# DDR4.net
KiCad netlist of a schematic drawn in Altium Designer
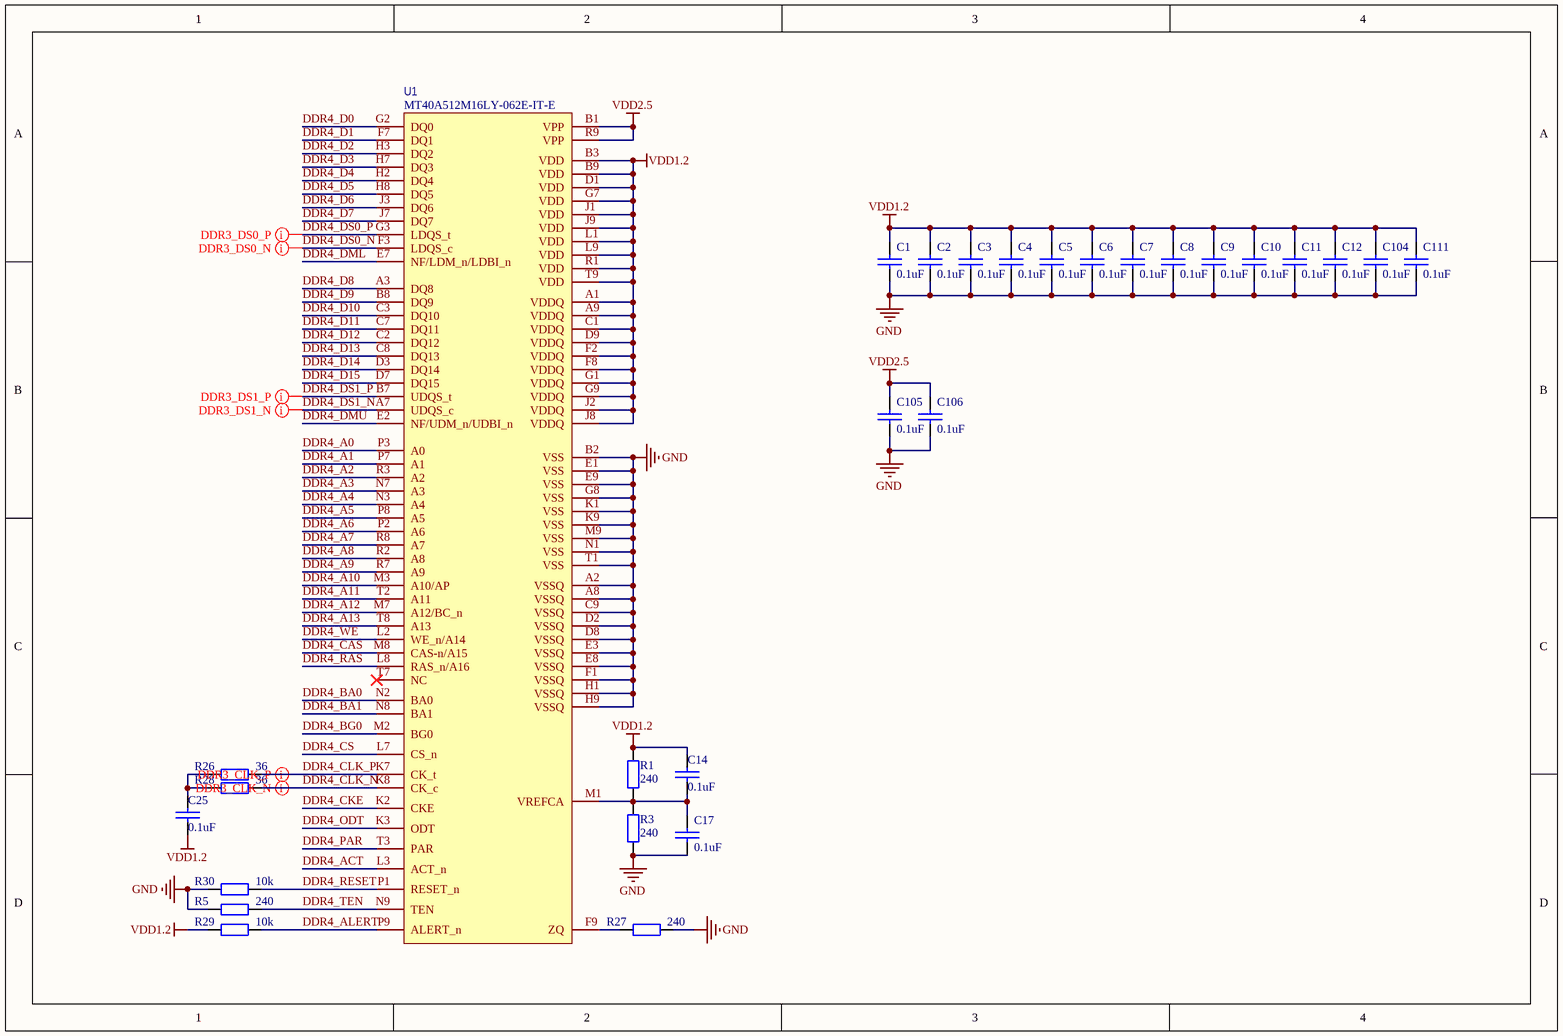
[diagram p0: DDR4.SchDoc]

(export (version "E")
  (design (tool "Eeschema 10.0.6"))
  (components
    (comp (ref "C1") (value "0.1uF") (footprint "0402_c_m") (libsource (lib "My library") (part "CAP")))
    (comp (ref "C2") (value "0.1uF") (footprint "0402_c_m") (libsource (lib "My library") (part "CAP")))
    (comp (ref "C3") (value "0.1uF") (footprint "0402_c_m") (libsource (lib "My library") (part "CAP")))
    (comp (ref "C4") (value "0.1uF") (footprint "0402_c_m") (libsource (lib "My library") (part "CAP")))
    (comp (ref "C5") (value "0.1uF") (footprint "0402_c_m") (libsource (lib "My library") (part "CAP")))
    (comp (ref "C6") (value "0.1uF") (footprint "0402_c_m") (libsource (lib "My library") (part "CAP")))
    (comp (ref "C7") (value "0.1uF") (footprint "0402_c_m") (libsource (lib "My library") (part "CAP")))
    (comp (ref "C8") (value "0.1uF") (footprint "0402_c_m") (libsource (lib "My library") (part "CAP")))
    (comp (ref "C9") (value "0.1uF") (footprint "0402_c_m") (libsource (lib "My library") (part "CAP")))
    (comp (ref "C10") (value "0.1uF") (footprint "0402_c_m") (libsource (lib "My library") (part "CAP")))
    (comp (ref "C11") (value "0.1uF") (footprint "0402_c_m") (libsource (lib "My library") (part "CAP")))
    (comp (ref "C12") (value "0.1uF") (footprint "0402_c_m") (libsource (lib "My library") (part "CAP")))
    (comp (ref "C14") (value "0.1uF") (footprint "0402_c_m") (libsource (lib "My library") (part "CAP")))
    (comp (ref "C17") (value "0.1uF") (footprint "0402_c_m") (libsource (lib "My library") (part "CAP")))
    (comp (ref "C25") (value "0.1uF") (footprint "0402_c_m") (libsource (lib "My library") (part "CAP")))
    (comp (ref "C104") (value "0.1uF") (footprint "0402_c_m") (libsource (lib "My library") (part "CAP")))
    (comp (ref "C105") (value "0.1uF") (footprint "0402_c_m") (libsource (lib "My library") (part "CAP")))
    (comp (ref "C106") (value "0.1uF") (footprint "0402_c_m") (libsource (lib "My library") (part "CAP")))
    (comp (ref "C111") (value "0.1uF") (footprint "0402_c_m") (libsource (lib "My library") (part "CAP")))
    (comp (ref "R1") (value "240") (footprint "0402_r_m") (libsource (lib "My Library") (part "RES2")))
    (comp (ref "R3") (value "240") (footprint "0402_r_m") (libsource (lib "My Library") (part "RES2")))
    (comp (ref "R5") (value "240") (footprint "0402_R_M") (libsource (lib "Common") (part "RES2")))
    (comp (ref "R26") (value "36") (footprint "0402_r_m") (libsource (lib "My Library") (part "RES2")))
    (comp (ref "R27") (value "240") (footprint "0402_R_M") (libsource (lib "Common") (part "RES2")))
    (comp (ref "R28") (value "36") (footprint "0402_r_m") (libsource (lib "My Library") (part "RES2")))
    (comp (ref "R29") (value "10k") (footprint "0402_r_m") (libsource (lib "My Library") (part "RES2")))
    (comp (ref "R30") (value "10k") (footprint "0402_r_m") (libsource (lib "My Library") (part "RES2")))
    (comp (ref "U1")
      (value "MT40A512M16LY-062E-IT-E")
      (footprint "MT40A512M16LY-062E-IT-E")
      (libsource (lib "MT40A512M16LY-062E-IT-E") (part "MT40A512M16LY-062E IT{colon}E"))
    )
  )
  (nets
    (net (code "1") (name "/DDR4_A0") (class "Default")
      (node (ref "U1") (pin "P3") (pinfunction "A0_P3") (pintype "passive"))
    )
    (net (code "2") (name "/DDR4_A1") (class "Default")
      (node (ref "U1") (pin "P7") (pinfunction "A1_P7") (pintype "passive"))
    )
    (net (code "3") (name "/DDR4_A2") (class "Default")
      (node (ref "U1") (pin "R3") (pinfunction "A2_R3") (pintype "passive"))
    )
    (net (code "4") (name "/DDR4_A3") (class "Default")
      (node (ref "U1") (pin "N7") (pinfunction "A3_N7") (pintype "passive"))
    )
    (net (code "5") (name "/DDR4_A4") (class "Default")
      (node (ref "U1") (pin "N3") (pinfunction "A4_N3") (pintype "passive"))
    )
    (net (code "6") (name "/DDR4_A5") (class "Default")
      (node (ref "U1") (pin "P8") (pinfunction "A5_P8") (pintype "passive"))
    )
    (net (code "7") (name "/DDR4_A6") (class "Default")
      (node (ref "U1") (pin "P2") (pinfunction "A6_P2") (pintype "passive"))
    )
    (net (code "8") (name "/DDR4_A7") (class "Default")
      (node (ref "U1") (pin "R8") (pinfunction "A7_R8") (pintype "passive"))
    )
    (net (code "9") (name "/DDR4_A8") (class "Default")
      (node (ref "U1") (pin "R2") (pinfunction "A8_R2") (pintype "passive"))
    )
    (net (code "10") (name "/DDR4_A9") (class "Default")
      (node (ref "U1") (pin "R7") (pinfunction "A9_R7") (pintype "passive"))
    )
    (net (code "11") (name "/DDR4_A10") (class "Default")
      (node (ref "U1") (pin "M3") (pinfunction "A10/AP_M3") (pintype "passive"))
    )
    (net (code "12") (name "/DDR4_A11") (class "Default")
      (node (ref "U1") (pin "T2") (pinfunction "A11_T2") (pintype "passive"))
    )
    (net (code "13") (name "/DDR4_A12") (class "Default")
      (node (ref "U1") (pin "M7") (pinfunction "A12/BC_n_M7") (pintype "passive"))
    )
    (net (code "14") (name "/DDR4_A13") (class "Default")
      (node (ref "U1") (pin "T8") (pinfunction "A13_T8") (pintype "passive"))
    )
    (net (code "15") (name "/DDR4_ACT") (class "Default")
      (node (ref "U1") (pin "L3") (pinfunction "ACT_n_L3") (pintype "passive"))
    )
    (net (code "16") (name "/DDR4_ALERT") (class "Default")
      (node (ref "R29") (pin "1") (pintype "passive"))
      (node (ref "U1") (pin "P9") (pinfunction "ALERT_n_P9") (pintype "passive"))
    )
    (net (code "17") (name "/DDR4_BA0") (class "Default")
      (node (ref "U1") (pin "N2") (pinfunction "BA0_N2") (pintype "passive"))
    )
    (net (code "18") (name "/DDR4_BA1") (class "Default")
      (node (ref "U1") (pin "N8") (pinfunction "BA1_N8") (pintype "passive"))
    )
    (net (code "19") (name "/DDR4_BG0") (class "Default")
      (node (ref "U1") (pin "M2") (pinfunction "BG0_M2") (pintype "passive"))
    )
    (net (code "20") (name "/DDR4_CAS") (class "Default")
      (node (ref "U1") (pin "M8") (pinfunction "CAS-n/A15_M8") (pintype "passive"))
    )
    (net (code "21") (name "/DDR4_CKE") (class "Default")
      (node (ref "U1") (pin "K2") (pinfunction "CKE_K2") (pintype "passive"))
    )
    (net (code "22") (name "/DDR4_CLK_N") (class "Default")
      (node (ref "R28") (pin "2") (pintype "passive"))
      (node (ref "U1") (pin "K8") (pinfunction "CK_c_K8") (pintype "passive"))
    )
    (net (code "23") (name "/DDR4_CLK_P") (class "Default")
      (node (ref "R26") (pin "2") (pintype "passive"))
      (node (ref "U1") (pin "K7") (pinfunction "CK_t_K7") (pintype "passive"))
    )
    (net (code "24") (name "/DDR4_CS") (class "Default")
      (node (ref "U1") (pin "L7") (pinfunction "CS_n_L7") (pintype "passive"))
    )
    (net (code "25") (name "/DDR4_D0") (class "Default")
      (node (ref "U1") (pin "G2") (pinfunction "DQ0_G2") (pintype "passive"))
    )
    (net (code "26") (name "/DDR4_D1") (class "Default")
      (node (ref "U1") (pin "F7") (pinfunction "DQ1_F7") (pintype "passive"))
    )
    (net (code "27") (name "/DDR4_D2") (class "Default")
      (node (ref "U1") (pin "H3") (pinfunction "DQ2_H3") (pintype "passive"))
    )
    (net (code "28") (name "/DDR4_D3") (class "Default")
      (node (ref "U1") (pin "H7") (pinfunction "DQ3_H7") (pintype "passive"))
    )
    (net (code "29") (name "/DDR4_D4") (class "Default")
      (node (ref "U1") (pin "H2") (pinfunction "DQ4_H2") (pintype "passive"))
    )
    (net (code "30") (name "/DDR4_D5") (class "Default")
      (node (ref "U1") (pin "H8") (pinfunction "DQ5_H8") (pintype "passive"))
    )
    (net (code "31") (name "/DDR4_D6") (class "Default")
      (node (ref "U1") (pin "J3") (pinfunction "DQ6_J3") (pintype "passive"))
    )
    (net (code "32") (name "/DDR4_D7") (class "Default")
      (node (ref "U1") (pin "J7") (pinfunction "DQ7_J7") (pintype "passive"))
    )
    (net (code "33") (name "/DDR4_D8") (class "Default")
      (node (ref "U1") (pin "A3") (pinfunction "DQ8_A3") (pintype "passive"))
    )
    (net (code "34") (name "/DDR4_D9") (class "Default")
      (node (ref "U1") (pin "B8") (pinfunction "DQ9_B8") (pintype "passive"))
    )
    (net (code "35") (name "/DDR4_D10") (class "Default")
      (node (ref "U1") (pin "C3") (pinfunction "DQ10_C3") (pintype "passive"))
    )
    (net (code "36") (name "/DDR4_D11") (class "Default")
      (node (ref "U1") (pin "C7") (pinfunction "DQ11_C7") (pintype "passive"))
    )
    (net (code "37") (name "/DDR4_D12") (class "Default")
      (node (ref "U1") (pin "C2") (pinfunction "DQ12_C2") (pintype "passive"))
    )
    (net (code "38") (name "/DDR4_D13") (class "Default")
      (node (ref "U1") (pin "C8") (pinfunction "DQ13_C8") (pintype "passive"))
    )
    (net (code "39") (name "/DDR4_D14") (class "Default")
      (node (ref "U1") (pin "D3") (pinfunction "DQ14_D3") (pintype "passive"))
    )
    (net (code "40") (name "/DDR4_D15") (class "Default")
      (node (ref "U1") (pin "D7") (pinfunction "DQ15_D7") (pintype "passive"))
    )
    (net (code "41") (name "/DDR4_DML") (class "Default")
      (node (ref "U1") (pin "E7") (pinfunction "NF/LDM_n/LDBI_n_E7") (pintype "passive"))
    )
    (net (code "42") (name "/DDR4_DMU") (class "Default")
      (node (ref "U1") (pin "E2") (pinfunction "NF/UDM_n/UDBI_n_E2") (pintype "passive"))
    )
    (net (code "43") (name "/DDR4_DS0_N") (class "Default")
      (node (ref "U1") (pin "F3") (pinfunction "LDQS_c_F3") (pintype "passive"))
    )
    (net (code "44") (name "/DDR4_DS0_P") (class "Default")
      (node (ref "U1") (pin "G3") (pinfunction "LDQS_t_G3") (pintype "passive"))
    )
    (net (code "45") (name "/DDR4_DS1_N") (class "Default")
      (node (ref "U1") (pin "A7") (pinfunction "UDQS_c_A7") (pintype "passive"))
    )
    (net (code "46") (name "/DDR4_DS1_P") (class "Default")
      (node (ref "U1") (pin "B7") (pinfunction "UDQS_t_B7") (pintype "passive"))
    )
    (net (code "47") (name "/DDR4_ODT") (class "Default")
      (node (ref "U1") (pin "K3") (pinfunction "ODT_K3") (pintype "passive"))
    )
    (net (code "48") (name "/DDR4_PAR") (class "Default")
      (node (ref "U1") (pin "T3") (pinfunction "PAR_T3") (pintype "passive"))
    )
    (net (code "49") (name "/DDR4_RAS") (class "Default")
      (node (ref "U1") (pin "L8") (pinfunction "RAS_n/A16_L8") (pintype "passive"))
    )
    (net (code "50") (name "/DDR4_RESET") (class "Default")
      (node (ref "R30") (pin "1") (pintype "passive"))
      (node (ref "U1") (pin "P1") (pinfunction "RESET_n_P1") (pintype "passive"))
    )
    (net (code "51") (name "/DDR4_TEN") (class "Default")
      (node (ref "R5") (pin "1") (pintype "passive"))
      (node (ref "U1") (pin "N9") (pinfunction "TEN_N9") (pintype "passive"))
    )
    (net (code "52") (name "/DDR4_WE") (class "Default")
      (node (ref "U1") (pin "L2") (pinfunction "WE_n/A14_L2") (pintype "passive"))
    )
    (net (code "53") (name "GND") (class "Default")
      (node (ref "C1") (pin "2") (pinfunction "2_2") (pintype "passive"))
      (node (ref "C10") (pin "2") (pinfunction "2_2") (pintype "passive"))
      (node (ref "C104") (pin "2") (pinfunction "2_2") (pintype "passive"))
      (node (ref "C105") (pin "2") (pinfunction "2_2") (pintype "passive"))
      (node (ref "C106") (pin "2") (pinfunction "2_2") (pintype "passive"))
      (node (ref "C11") (pin "2") (pinfunction "2_2") (pintype "passive"))
      (node (ref "C111") (pin "2") (pinfunction "2_2") (pintype "passive"))
      (node (ref "C12") (pin "2") (pinfunction "2_2") (pintype "passive"))
      (node (ref "C17") (pin "2") (pinfunction "2_2") (pintype "passive"))
      (node (ref "C2") (pin "2") (pinfunction "2_2") (pintype "passive"))
      (node (ref "C3") (pin "2") (pinfunction "2_2") (pintype "passive"))
      (node (ref "C4") (pin "2") (pinfunction "2_2") (pintype "passive"))
      (node (ref "C5") (pin "2") (pinfunction "2_2") (pintype "passive"))
      (node (ref "C6") (pin "2") (pinfunction "2_2") (pintype "passive"))
      (node (ref "C7") (pin "2") (pinfunction "2_2") (pintype "passive"))
      (node (ref "C8") (pin "2") (pinfunction "2_2") (pintype "passive"))
      (node (ref "C9") (pin "2") (pinfunction "2_2") (pintype "passive"))
      (node (ref "R27") (pin "1") (pintype "passive"))
      (node (ref "R3") (pin "1") (pintype "passive"))
      (node (ref "R30") (pin "2") (pintype "passive"))
      (node (ref "R5") (pin "2") (pintype "passive"))
      (node (ref "U1") (pin "A2") (pinfunction "VSSQ_A2") (pintype "passive"))
      (node (ref "U1") (pin "A8") (pinfunction "VSSQ_A8") (pintype "passive"))
      (node (ref "U1") (pin "B2") (pinfunction "VSS_B2") (pintype "passive"))
      (node (ref "U1") (pin "C9") (pinfunction "VSSQ_C9") (pintype "passive"))
      (node (ref "U1") (pin "D2") (pinfunction "VSSQ_D2") (pintype "passive"))
      (node (ref "U1") (pin "D8") (pinfunction "VSSQ_D8") (pintype "passive"))
      (node (ref "U1") (pin "E1") (pinfunction "VSS_E1") (pintype "passive"))
      (node (ref "U1") (pin "E3") (pinfunction "VSSQ_E3") (pintype "passive"))
      (node (ref "U1") (pin "E8") (pinfunction "VSSQ_E8") (pintype "passive"))
      (node (ref "U1") (pin "E9") (pinfunction "VSS_E9") (pintype "passive"))
      (node (ref "U1") (pin "F1") (pinfunction "VSSQ_F1") (pintype "passive"))
      (node (ref "U1") (pin "G8") (pinfunction "VSS_G8") (pintype "passive"))
      (node (ref "U1") (pin "H1") (pinfunction "VSSQ_H1") (pintype "passive"))
      (node (ref "U1") (pin "H9") (pinfunction "VSSQ_H9") (pintype "passive"))
      (node (ref "U1") (pin "K1") (pinfunction "VSS_K1") (pintype "passive"))
      (node (ref "U1") (pin "K9") (pinfunction "VSS_K9") (pintype "passive"))
      (node (ref "U1") (pin "M9") (pinfunction "VSS_M9") (pintype "passive"))
      (node (ref "U1") (pin "N1") (pinfunction "VSS_N1") (pintype "passive"))
      (node (ref "U1") (pin "T1") (pinfunction "VSS_T1") (pintype "passive"))
    )
    (net (code "54") (name "Net-(C25-Pad2)") (class "Default")
      (node (ref "C25") (pin "2") (pinfunction "2_2") (pintype "passive"))
      (node (ref "R26") (pin "1") (pintype "passive"))
      (node (ref "R28") (pin "1") (pintype "passive"))
    )
    (net (code "55") (name "Net-(U1-VREFCA)") (class "Default")
      (node (ref "C14") (pin "2") (pinfunction "2_2") (pintype "passive"))
      (node (ref "C17") (pin "1") (pinfunction "1_1") (pintype "passive"))
      (node (ref "R1") (pin "1") (pintype "passive"))
      (node (ref "R3") (pin "2") (pintype "passive"))
      (node (ref "U1") (pin "M1") (pinfunction "VREFCA_M1") (pintype "passive"))
    )
    (net (code "56") (name "Net-(U1-ZQ)") (class "Default")
      (node (ref "R27") (pin "2") (pintype "passive"))
      (node (ref "U1") (pin "F9") (pinfunction "ZQ_F9") (pintype "passive"))
    )
    (net (code "57") (name "VDD1.2") (class "Default")
      (node (ref "C1") (pin "1") (pinfunction "1_1") (pintype "passive"))
      (node (ref "C10") (pin "1") (pinfunction "1_1") (pintype "passive"))
      (node (ref "C104") (pin "1") (pinfunction "1_1") (pintype "passive"))
      (node (ref "C11") (pin "1") (pinfunction "1_1") (pintype "passive"))
      (node (ref "C111") (pin "1") (pinfunction "1_1") (pintype "passive"))
      (node (ref "C12") (pin "1") (pinfunction "1_1") (pintype "passive"))
      (node (ref "C14") (pin "1") (pinfunction "1_1") (pintype "passive"))
      (node (ref "C2") (pin "1") (pinfunction "1_1") (pintype "passive"))
      (node (ref "C25") (pin "1") (pinfunction "1_1") (pintype "passive"))
      (node (ref "C3") (pin "1") (pinfunction "1_1") (pintype "passive"))
      (node (ref "C4") (pin "1") (pinfunction "1_1") (pintype "passive"))
      (node (ref "C5") (pin "1") (pinfunction "1_1") (pintype "passive"))
      (node (ref "C6") (pin "1") (pinfunction "1_1") (pintype "passive"))
      (node (ref "C7") (pin "1") (pinfunction "1_1") (pintype "passive"))
      (node (ref "C8") (pin "1") (pinfunction "1_1") (pintype "passive"))
      (node (ref "C9") (pin "1") (pinfunction "1_1") (pintype "passive"))
      (node (ref "R1") (pin "2") (pintype "passive"))
      (node (ref "R29") (pin "2") (pintype "passive"))
      (node (ref "U1") (pin "A1") (pinfunction "VDDQ_A1") (pintype "passive"))
      (node (ref "U1") (pin "A9") (pinfunction "VDDQ_A9") (pintype "passive"))
      (node (ref "U1") (pin "B3") (pinfunction "VDD_B3") (pintype "passive"))
      (node (ref "U1") (pin "B9") (pinfunction "VDD_B9") (pintype "passive"))
      (node (ref "U1") (pin "C1") (pinfunction "VDDQ_C1") (pintype "passive"))
      (node (ref "U1") (pin "D1") (pinfunction "VDD_D1") (pintype "passive"))
      (node (ref "U1") (pin "D9") (pinfunction "VDDQ_D9") (pintype "passive"))
      (node (ref "U1") (pin "F2") (pinfunction "VDDQ_F2") (pintype "passive"))
      (node (ref "U1") (pin "F8") (pinfunction "VDDQ_F8") (pintype "passive"))
      (node (ref "U1") (pin "G1") (pinfunction "VDDQ_G1") (pintype "passive"))
      (node (ref "U1") (pin "G7") (pinfunction "VDD_G7") (pintype "passive"))
      (node (ref "U1") (pin "G9") (pinfunction "VDDQ_G9") (pintype "passive"))
      (node (ref "U1") (pin "J1") (pinfunction "VDD_J1") (pintype "passive"))
      (node (ref "U1") (pin "J2") (pinfunction "VDDQ_J2") (pintype "passive"))
      (node (ref "U1") (pin "J8") (pinfunction "VDDQ_J8") (pintype "passive"))
      (node (ref "U1") (pin "J9") (pinfunction "VDD_J9") (pintype "passive"))
      (node (ref "U1") (pin "L1") (pinfunction "VDD_L1") (pintype "passive"))
      (node (ref "U1") (pin "L9") (pinfunction "VDD_L9") (pintype "passive"))
      (node (ref "U1") (pin "R1") (pinfunction "VDD_R1") (pintype "passive"))
      (node (ref "U1") (pin "T9") (pinfunction "VDD_T9") (pintype "passive"))
    )
    (net (code "58") (name "VDD2.5") (class "Default")
      (node (ref "C105") (pin "1") (pinfunction "1_1") (pintype "passive"))
      (node (ref "C106") (pin "1") (pinfunction "1_1") (pintype "passive"))
      (node (ref "U1") (pin "B1") (pinfunction "VPP_B1") (pintype "passive"))
      (node (ref "U1") (pin "R9") (pinfunction "VPP_R9") (pintype "passive"))
    )
    (net (code "59") (name "unconnected-(U1-NC-PadT7)") (class "Default")
      (node (ref "U1") (pin "T7") (pinfunction "NC_T7") (pintype "passive+no_connect"))
    )
  )
)
